# Main.net
KiCad netlist of a schematic drawn in Altium Designer
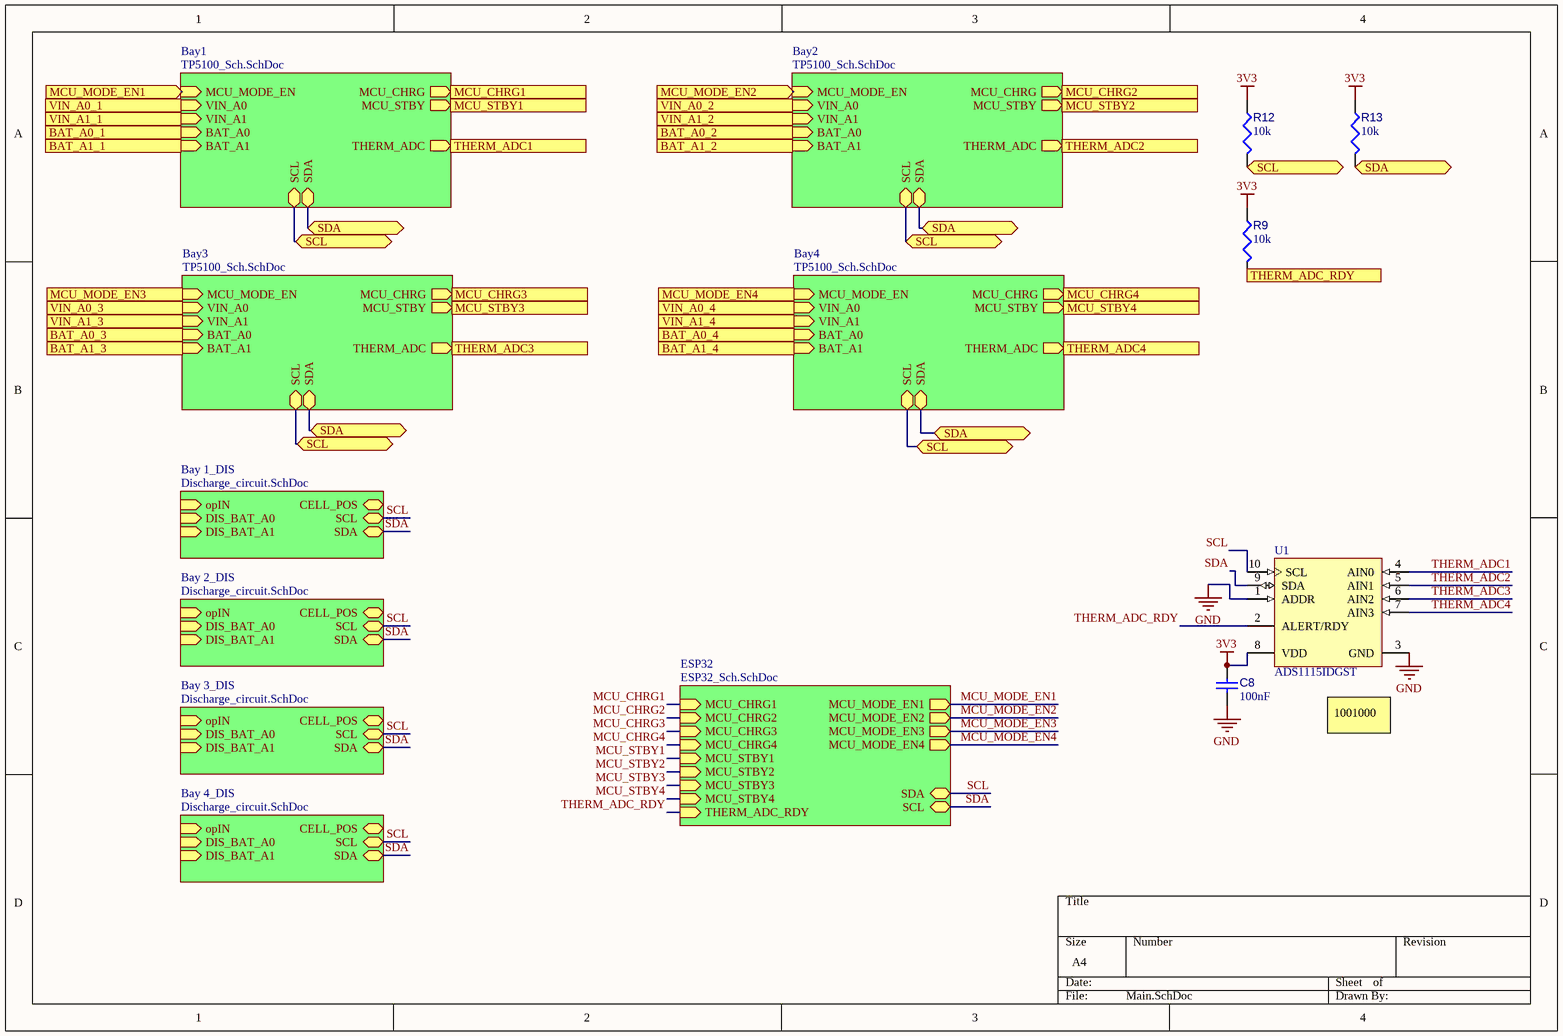
[diagram p0: Main.SchDoc]

(export (version "E")
  (design (tool "Eeschema 10.0.6"))
  (components
    (comp (ref "C8")
      (value "100nF")
      (footprint "CAPC1005X56X25LL10T15")
      (description "Chip Capacitor, 0.1 uF, +/- 5%, 16 V, 0402 (1005 Metric)")
      (fields (field (name "TOLERANCE") "5%") (field (name "Comment") "Capacitor 0.1 uF +/- 5% 16 V 0402"))
      (libsource (lib "ZionTech") (part "CAP-NP-2"))
    )
    (comp (ref "R9")
      (value "10k")
      (footprint "RESC0402(1005)_L")
      (description "10K 0.063W 1% 0402 (1005 Metric)  SMD")
      (fields (field (name "POWER") "63mW") (field (name "TOLERANCE") "1%"))
      (libsource (lib "ZionTech") (part "10KR2F"))
    )
    (comp (ref "R12")
      (value "10k")
      (footprint "RESC0402(1005)_L")
      (description "10K 0.063W 1% 0402 (1005 Metric)  SMD")
      (fields (field (name "POWER") "63mW") (field (name "TOLERANCE") "1%"))
      (libsource (lib "ZionTech") (part "10KR2F"))
    )
    (comp (ref "R13")
      (value "10k")
      (footprint "RESC0402(1005)_L")
      (description "10K 0.063W 1% 0402 (1005 Metric)  SMD")
      (fields (field (name "POWER") "63mW") (field (name "TOLERANCE") "1%"))
      (libsource (lib "ZionTech") (part "10KR2F"))
    )
    (comp (ref "U1")
      (value "ADS1115IDGST")
      (footprint "TI-DGS10_M")
      (fields (field (name "MANUFACTURER") "Texas Instruments"))
      (libsource (lib "Altium Content Vault") (part "TI-ADS1015_1115-10"))
    )
  )
  (nets
    (net (code "33") (name "/SCL") (class "Default")
      (node (ref "U1") (pin "10") (pinfunction "SCL_10") (pintype "input"))
    )
    (net (code "34") (name "/SDA") (class "Default")
      (node (ref "U1") (pin "9") (pinfunction "SDA_9") (pintype "bidirectional"))
    )
    (net (code "35") (name "/THERM_ADC1") (class "Default")
      (node (ref "U1") (pin "4") (pinfunction "AIN0_4") (pintype "input"))
    )
    (net (code "36") (name "/THERM_ADC2") (class "Default")
      (node (ref "U1") (pin "5") (pinfunction "AIN1_5") (pintype "input"))
    )
    (net (code "37") (name "/THERM_ADC3") (class "Default")
      (node (ref "U1") (pin "6") (pinfunction "AIN2_6") (pintype "input"))
    )
    (net (code "38") (name "/THERM_ADC4") (class "Default")
      (node (ref "U1") (pin "7") (pinfunction "AIN3_7") (pintype "input"))
    )
    (net (code "39") (name "/THERM_ADC_RDY") (class "Default")
      (node (ref "U1") (pin "2") (pinfunction "ALERT/RDY_2") (pintype "open_collector"))
    )
    (net (code "52") (name "3V3") (class "Default")
      (node (ref "C8") (pin "1") (pinfunction "1_1") (pintype "passive"))
      (node (ref "R12") (pin "1") (pinfunction "1_1") (pintype "passive"))
      (node (ref "R13") (pin "1") (pinfunction "1_1") (pintype "passive"))
      (node (ref "R9") (pin "1") (pinfunction "1_1") (pintype "passive"))
      (node (ref "U1") (pin "8") (pinfunction "VDD_8") (pintype "power_in"))
    )
    (net (code "53") (name "GND") (class "Default")
      (node (ref "C8") (pin "2") (pinfunction "2_2") (pintype "passive"))
      (node (ref "U1") (pin "1") (pinfunction "ADDR_1") (pintype "input"))
      (node (ref "U1") (pin "3") (pinfunction "GND_3") (pintype "power_in"))
    )
    (net (code "54") (name "unconnected-(R9-Pad2)") (class "Default")
      (node (ref "R9") (pin "2") (pinfunction "2_2") (pintype "passive"))
    )
    (net (code "55") (name "unconnected-(R12-Pad2)") (class "Default")
      (node (ref "R12") (pin "2") (pinfunction "2_2") (pintype "passive"))
    )
    (net (code "56") (name "unconnected-(R13-Pad2)") (class "Default")
      (node (ref "R13") (pin "2") (pinfunction "2_2") (pintype "passive"))
    )
  )
)
